# sb-sonata-fpga.net
KiCad netlist of a schematic drawn in Altium Designer
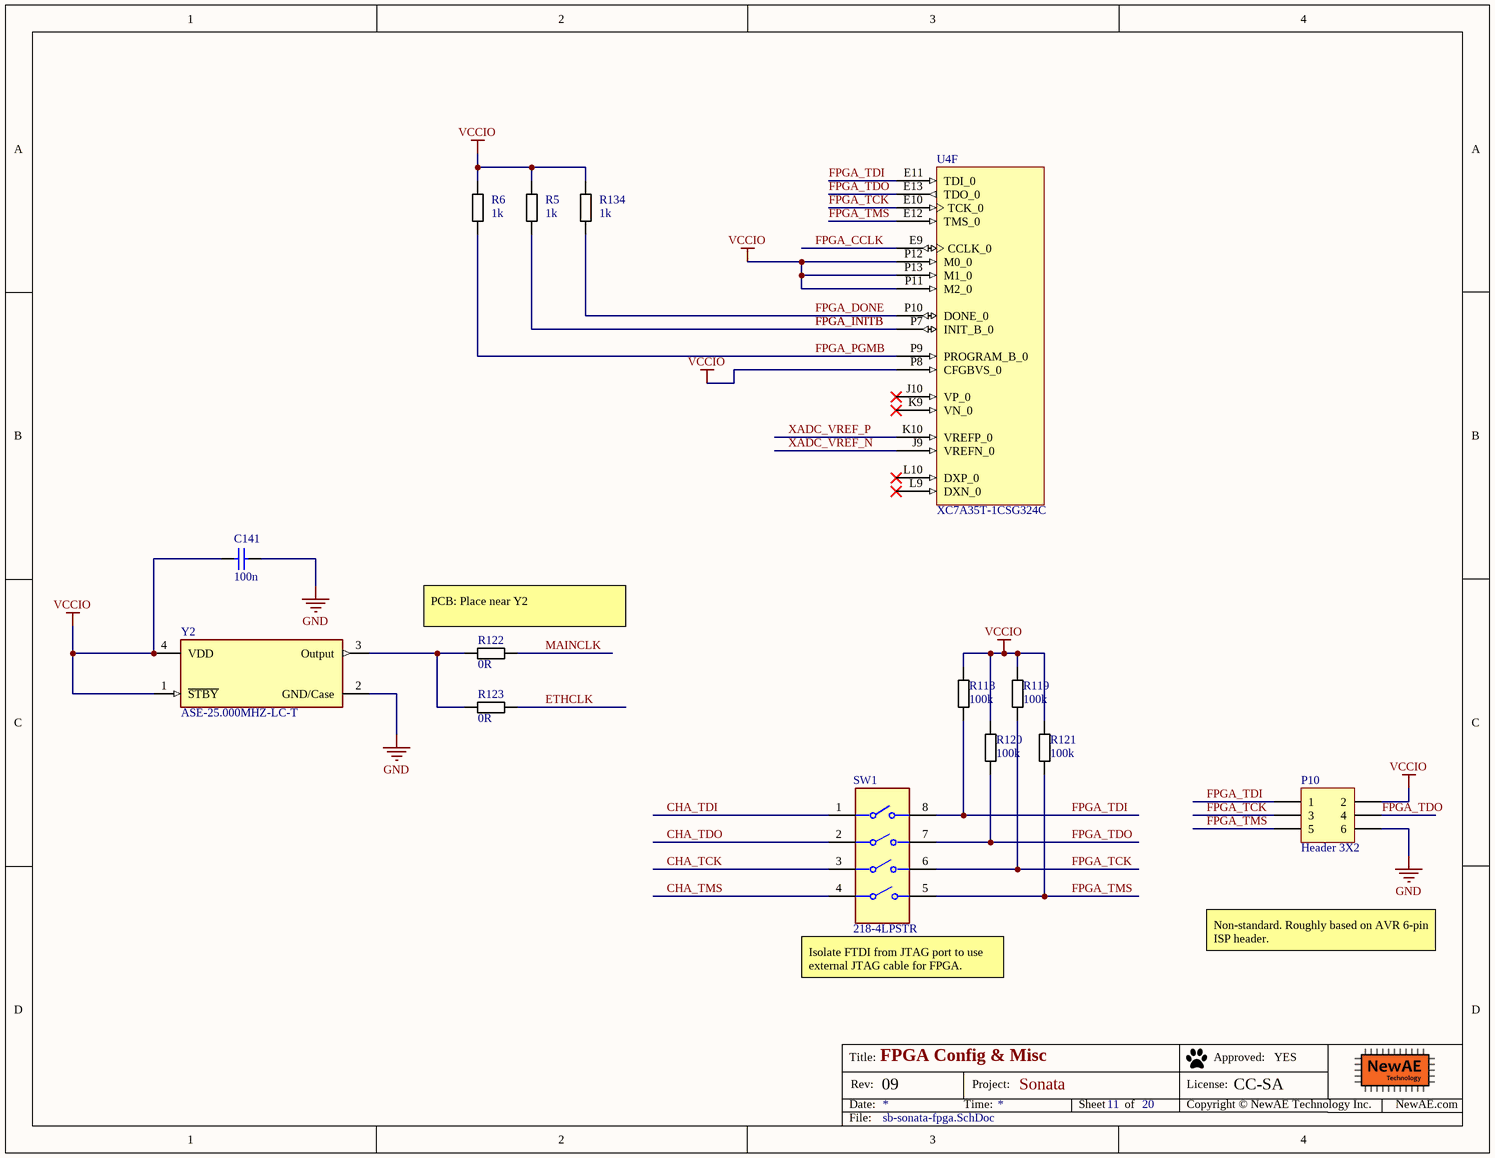
[diagram p0: sb-sonata-fpga.SchDoc]

(export (version "E")
  (design (tool "Eeschema 10.0.6"))
  (components
    (comp (ref "C141")
      (value "100n")
      (footprint "CAPC0402_M")
      (description "100n, 0402")
      (fields (field (name "PART NUMBER") "CCHIP-100n-0402"))
      (libsource (lib "NewAE_AltiumLib") (part "CAP"))
    )
    (comp (ref "P10")
      (value "Header 3X2")
      (footprint "HDR2X3")
      (description "Header, 3-Pin, Dual row")
      (fields (field (name "PUBLISHER") "Altium Limited"))
      (libsource (lib "Miscellaneous Connectors") (part "Header 3X2"))
    )
    (comp (ref "R5")
      (value "1k")
      (footprint "RESC1608X55N")
      (description "1k res, 0603, 1%, 1/10W")
      (fields (field (name "PART NUMBER") "RCHIP-1K-0603") (field (name "TOLERANCE") "1%"))
      (libsource (lib "NewAE_AltiumLib") (part "RES-EU"))
    )
    (comp (ref "R6")
      (value "1k")
      (footprint "RESC1608X55N")
      (description "1k res, 0603, 1%, 1/10W")
      (fields (field (name "PART NUMBER") "RCHIP-1K-0603") (field (name "TOLERANCE") "1%"))
      (libsource (lib "NewAE_AltiumLib") (part "RES-EU"))
    )
    (comp (ref "R118")
      (value "100k")
      (footprint "RESC1005X40N")
      (description "100k res, 0402, 1%, 1/16W")
      (fields (field (name "PART NUMBER") "RCHIP-100K-0402") (field (name "TOLERANCE") "1%"))
      (libsource (lib "NewAE_AltiumLib") (part "RES-EU"))
    )
    (comp (ref "R119")
      (value "100k")
      (footprint "RESC1005X40N")
      (description "100k res, 0402, 1%, 1/16W")
      (fields (field (name "PART NUMBER") "RCHIP-100K-0402") (field (name "TOLERANCE") "1%"))
      (libsource (lib "NewAE_AltiumLib") (part "RES-EU"))
    )
    (comp (ref "R120")
      (value "100k")
      (footprint "RESC1005X40N")
      (description "100k res, 0402, 1%, 1/16W")
      (fields (field (name "PART NUMBER") "RCHIP-100K-0402") (field (name "TOLERANCE") "1%"))
      (libsource (lib "NewAE_AltiumLib") (part "RES-EU"))
    )
    (comp (ref "R121")
      (value "100k")
      (footprint "RESC1005X40N")
      (description "100k res, 0402, 1%, 1/16W")
      (fields (field (name "PART NUMBER") "RCHIP-100K-0402") (field (name "TOLERANCE") "1%"))
      (libsource (lib "NewAE_AltiumLib") (part "RES-EU"))
    )
    (comp (ref "R122")
      (value "0R")
      (footprint "RESC1608X55N")
      (description "0R, 0603, 1/10W")
      (fields (field (name "PART NUMBER") "RCHIP-0R-0603") (field (name "TOLERANCE") "1%"))
      (libsource (lib "") (part "RES-EU_1"))
    )
    (comp (ref "R123")
      (value "0R")
      (footprint "RESC1608X55N")
      (description "0R, 0603, 1/10W")
      (fields (field (name "PART NUMBER") "RCHIP-0R-0603") (field (name "TOLERANCE") "1%"))
      (libsource (lib "") (part "RES-EU_1"))
    )
    (comp (ref "R134")
      (value "1k")
      (footprint "RESC1608X55N")
      (description "1k res, 0603, 1%, 1/10W")
      (fields (field (name "PART NUMBER") "RCHIP-1K-0603") (field (name "TOLERANCE") "1%"))
      (libsource (lib "NewAE_AltiumLib") (part "RES-EU"))
    )
    (comp (ref "SW1")
      (value "218-4LPSTR")
      (footprint "FP-218-4LPSTR-MFG")
      (description "SWITCH SLIDE DIP SPST 25MA 24V")
      (libsource (lib "Altium Content Vault") (part "a78650ae27aee94b64e9c93150c7d5d"))
    )
    (comp (ref "U4")
      (value "XC7A35T-1CSG324C")
      (footprint "CSG324")
      (description "Artix-7 FPGA, 210 User I/Os, 0 GTP, 324-Ball BGA, Speed Grade 1, Commercial Grade, Pb-Free")
      (fields (field (name "MANUFACTURER") "Xilinx"))
      (libsource (lib "Altium Content Vault") (part "XLNX-XC7A35T-CSG324"))
    )
    (comp (ref "Y2")
      (value "ASE-25.000MHZ-LC-T")
      (footprint "FP-ASE-MFG")
      (description "XTAL Oscillator 25MHz ±50ppm CMOS 3.3V 4-SMD 3.2mm x 2.5mm")
      (libsource (lib "Altium Content Vault") (part "61a724e6190563596ac712fef61ad37"))
    )
  )
  (nets
    (net (code "1") (name "/CHA_TCK") (class "Default")
      (node (ref "SW1") (pin "3") (pinfunction "3_3") (pintype "passive"))
    )
    (net (code "2") (name "/CHA_TDI") (class "Default")
      (node (ref "SW1") (pin "1") (pinfunction "1_1") (pintype "passive"))
    )
    (net (code "3") (name "/CHA_TDO") (class "Default")
      (node (ref "SW1") (pin "2") (pinfunction "2_2") (pintype "passive"))
    )
    (net (code "4") (name "/CHA_TMS") (class "Default")
      (node (ref "SW1") (pin "4") (pinfunction "4_4") (pintype "passive"))
    )
    (net (code "5") (name "/ETHCLK") (class "Default")
      (node (ref "R123") (pin "2") (pinfunction "2_2") (pintype "passive"))
    )
    (net (code "6") (name "/FPGA_CCLK") (class "Default")
      (node (ref "U4") (pin "E9") (pinfunction "CCLK_0_E9") (pintype "bidirectional"))
    )
    (net (code "7") (name "/FPGA_DONE") (class "Default")
      (node (ref "R134") (pin "2") (pinfunction "2_2") (pintype "passive"))
      (node (ref "U4") (pin "P10") (pinfunction "DONE_0_P10") (pintype "bidirectional"))
    )
    (net (code "8") (name "/FPGA_INITB") (class "Default")
      (node (ref "R5") (pin "2") (pinfunction "2_2") (pintype "passive"))
      (node (ref "U4") (pin "P7") (pinfunction "INIT_B_0_P7") (pintype "bidirectional"))
    )
    (net (code "9") (name "/FPGA_PGMB") (class "Default")
      (node (ref "R6") (pin "2") (pinfunction "2_2") (pintype "passive"))
      (node (ref "U4") (pin "P9") (pinfunction "PROGRAM_B_0_P9") (pintype "input"))
    )
    (net (code "10") (name "/FPGA_TCK") (class "Default")
      (node (ref "P10") (pin "3") (pinfunction "3_3") (pintype "passive"))
      (node (ref "R119") (pin "2") (pinfunction "2_2") (pintype "passive"))
      (node (ref "SW1") (pin "6") (pinfunction "6_6") (pintype "passive"))
      (node (ref "U4") (pin "E10") (pinfunction "TCK_0_E10") (pintype "input"))
    )
    (net (code "11") (name "/FPGA_TDI") (class "Default")
      (node (ref "P10") (pin "1") (pinfunction "1_1") (pintype "passive"))
      (node (ref "R118") (pin "2") (pinfunction "2_2") (pintype "passive"))
      (node (ref "SW1") (pin "8") (pinfunction "8_8") (pintype "passive"))
      (node (ref "U4") (pin "E11") (pinfunction "TDI_0_E11") (pintype "input"))
    )
    (net (code "12") (name "/FPGA_TDO") (class "Default")
      (node (ref "P10") (pin "4") (pinfunction "4_4") (pintype "passive"))
      (node (ref "R120") (pin "2") (pinfunction "2_2") (pintype "passive"))
      (node (ref "SW1") (pin "7") (pinfunction "7_7") (pintype "passive"))
      (node (ref "U4") (pin "E13") (pinfunction "TDO_0_E13") (pintype "output"))
    )
    (net (code "13") (name "/FPGA_TMS") (class "Default")
      (node (ref "P10") (pin "5") (pinfunction "5_5") (pintype "passive"))
      (node (ref "R121") (pin "2") (pinfunction "2_2") (pintype "passive"))
      (node (ref "SW1") (pin "5") (pinfunction "5_5") (pintype "passive"))
      (node (ref "U4") (pin "E12") (pinfunction "TMS_0_E12") (pintype "input"))
    )
    (net (code "14") (name "/MAINCLK") (class "Default")
      (node (ref "R122") (pin "2") (pinfunction "2_2") (pintype "passive"))
    )
    (net (code "15") (name "/XADC_VREF_N") (class "Default")
      (node (ref "U4") (pin "J9") (pinfunction "VREFN_0_J9") (pintype "input"))
    )
    (net (code "16") (name "/XADC_VREF_P") (class "Default")
      (node (ref "U4") (pin "K10") (pinfunction "VREFP_0_K10") (pintype "input"))
    )
    (net (code "17") (name "GND") (class "Default")
      (node (ref "C141") (pin "2") (pinfunction "2_2") (pintype "passive"))
      (node (ref "P10") (pin "6") (pinfunction "6_6") (pintype "passive"))
      (node (ref "Y2") (pin "2") (pinfunction "GND/Case_2") (pintype "power_in"))
    )
    (net (code "18") (name "Net-(Y2-Output)") (class "Default")
      (node (ref "R122") (pin "1") (pinfunction "1_1") (pintype "passive"))
      (node (ref "R123") (pin "1") (pinfunction "1_1") (pintype "passive"))
      (node (ref "Y2") (pin "3") (pinfunction "Output_3") (pintype "output"))
    )
    (net (code "19") (name "VCCIO") (class "Default")
      (node (ref "C141") (pin "1") (pinfunction "1_1") (pintype "passive"))
      (node (ref "P10") (pin "2") (pinfunction "2_2") (pintype "passive"))
      (node (ref "R118") (pin "1") (pinfunction "1_1") (pintype "passive"))
      (node (ref "R119") (pin "1") (pinfunction "1_1") (pintype "passive"))
      (node (ref "R120") (pin "1") (pinfunction "1_1") (pintype "passive"))
      (node (ref "R121") (pin "1") (pinfunction "1_1") (pintype "passive"))
      (node (ref "R134") (pin "1") (pinfunction "1_1") (pintype "passive"))
      (node (ref "R5") (pin "1") (pinfunction "1_1") (pintype "passive"))
      (node (ref "R6") (pin "1") (pinfunction "1_1") (pintype "passive"))
      (node (ref "U4") (pin "P11") (pinfunction "M2_0_P11") (pintype "input"))
      (node (ref "U4") (pin "P12") (pinfunction "M0_0_P12") (pintype "input"))
      (node (ref "U4") (pin "P13") (pinfunction "M1_0_P13") (pintype "input"))
      (node (ref "U4") (pin "P8") (pinfunction "CFGBVS_0_P8") (pintype "input"))
      (node (ref "Y2") (pin "1") (pinfunction "~{STBY}_1") (pintype "input"))
      (node (ref "Y2") (pin "4") (pinfunction "VDD_4") (pintype "power_in"))
    )
    (net (code "20") (name "unconnected-(U4F-DXN_0-PadL9)") (class "Default")
      (node (ref "U4") (pin "L9") (pinfunction "DXN_0_L9") (pintype "input+no_connect"))
    )
    (net (code "21") (name "unconnected-(U4F-DXP_0-PadL10)") (class "Default")
      (node (ref "U4") (pin "L10") (pinfunction "DXP_0_L10") (pintype "input+no_connect"))
    )
    (net (code "22") (name "unconnected-(U4F-VN_0-PadK9)") (class "Default")
      (node (ref "U4") (pin "K9") (pinfunction "VN_0_K9") (pintype "input+no_connect"))
    )
    (net (code "23") (name "unconnected-(U4F-VP_0-PadJ10)") (class "Default")
      (node (ref "U4") (pin "J10") (pinfunction "VP_0_J10") (pintype "input+no_connect"))
    )
  )
)
